# esp32_s20.net
KiCad netlist of a schematic drawn in EAGLE
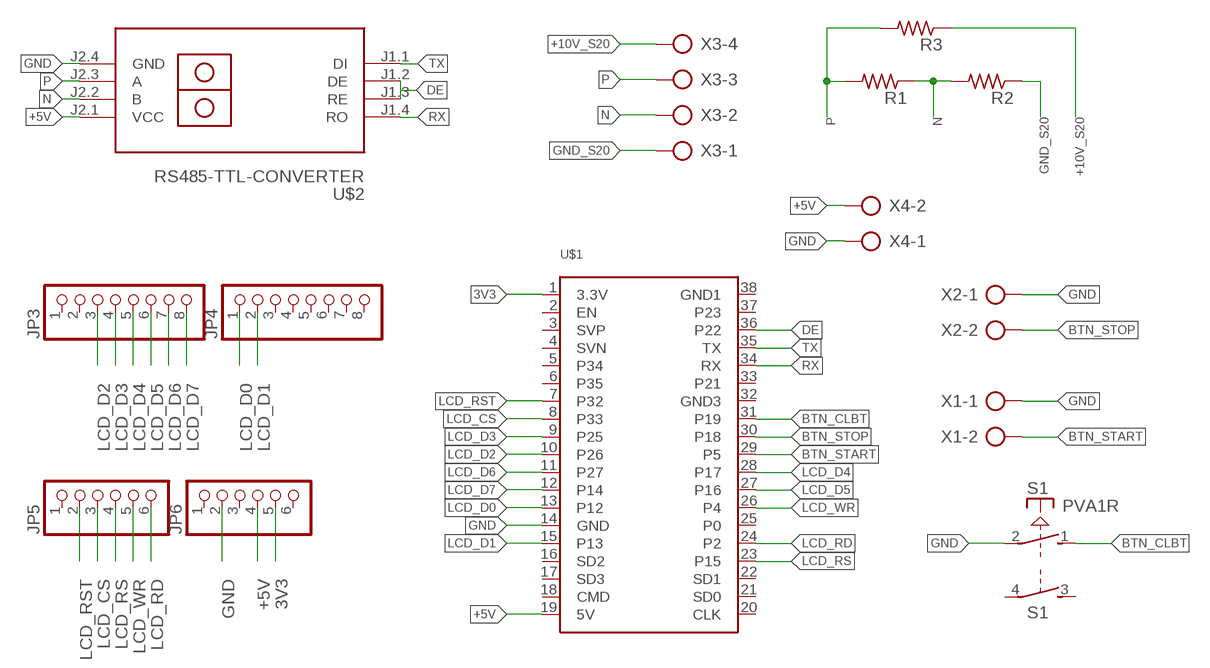
[diagram p0: schematic, sheet 1]

(export (version "E")
  (design (tool "Eeschema 10.0.6"))
  (components
    (comp (ref "JP3")
      (value "PINHD-1X8")
      (footprint "eagle-import:1X08")
      (libsource (lib "eagle-import") (part "PINHD-1X8"))
    )
    (comp (ref "JP4")
      (value "PINHD-1X8")
      (footprint "eagle-import:1X08")
      (libsource (lib "eagle-import") (part "PINHD-1X8"))
    )
    (comp (ref "JP5")
      (value "PINHD-1X6")
      (footprint "eagle-import:1X06")
      (libsource (lib "eagle-import") (part "PINHD-1X6"))
    )
    (comp (ref "JP6")
      (value "PINHD-1X6")
      (footprint "eagle-import:1X06")
      (libsource (lib "eagle-import") (part "PINHD-1X6"))
    )
    (comp (ref "R1")
      (value "R-US_0204/7")
      (footprint "eagle-import:0204_7")
      (libsource (lib "eagle-import") (part "R-US_0204/7"))
    )
    (comp (ref "R2")
      (value "R-US_0204/7")
      (footprint "eagle-import:0204_7")
      (libsource (lib "eagle-import") (part "R-US_0204/7"))
    )
    (comp (ref "R3")
      (value "R-US_0204/7")
      (footprint "eagle-import:0204_7")
      (libsource (lib "eagle-import") (part "R-US_0204/7"))
    )
    (comp (ref "S1")
      (value "PVA1R")
      (footprint "eagle-import:PVA1R")
      (libsource (lib "eagle-import") (part "PVA1R"))
    )
    (comp (ref "U$1")
      (value "ESP-32S")
      (footprint "eagle-import:BOARD")
      (libsource (lib "eagle-import") (part "ESP-32S"))
    )
    (comp (ref "U$2")
      (value "RS485-TTL-CONVERTER")
      (footprint "eagle-import:RS485-TTL-CONVERTER")
      (libsource (lib "eagle-import") (part "RS485-TTL-CONVERTER"))
    )
    (comp (ref "X1")
      (value "AK500/2-H")
      (footprint "eagle-import:AK500_2-H")
      (libsource (lib "eagle-import") (part "AK500/2-H"))
    )
    (comp (ref "X2")
      (value "AK500/2-H")
      (footprint "eagle-import:AK500_2-H")
      (libsource (lib "eagle-import") (part "AK500/2-H"))
    )
    (comp (ref "X3")
      (value "AK500/4-H")
      (footprint "eagle-import:AK500_4-H")
      (libsource (lib "eagle-import") (part "AK500/4-H"))
    )
    (comp (ref "X4")
      (value "AK500/2-H")
      (footprint "eagle-import:AK500_2-H")
      (libsource (lib "eagle-import") (part "AK500/2-H"))
    )
  )
  (nets
    (net (code "1") (name "+5V") (class "Default")
      (node (ref "JP6") (pin "4") (pinfunction "4_4") (pintype "passive"))
      (node (ref "U$1") (pin "19") (pinfunction "5V_19") (pintype "bidirectional"))
      (node (ref "U$2") (pin "J2.1") (pinfunction "VCC_J2.1") (pintype "power_in"))
      (node (ref "X4") (pin "2") (pinfunction "KL_2") (pintype "passive"))
    )
    (net (code "2") (name "+10V_S20") (class "Default")
      (node (ref "R3") (pin "1") (pinfunction "1_1") (pintype "passive"))
      (node (ref "X3") (pin "4") (pinfunction "KL_4") (pintype "passive"))
    )
    (net (code "3") (name "3V3") (class "Default")
      (node (ref "JP6") (pin "5") (pinfunction "5_5") (pintype "passive"))
      (node (ref "U$1") (pin "1") (pinfunction "3.3V_1") (pintype "bidirectional"))
    )
    (net (code "4") (name "BTN_CLBT") (class "Default")
      (node (ref "S1") (pin "1") (pinfunction "S_1") (pintype "passive"))
      (node (ref "U$1") (pin "31") (pinfunction "P19_31") (pintype "bidirectional"))
    )
    (net (code "5") (name "BTN_START") (class "Default")
      (node (ref "U$1") (pin "29") (pinfunction "P5_29") (pintype "bidirectional"))
      (node (ref "X1") (pin "2") (pinfunction "KL_2") (pintype "passive"))
    )
    (net (code "6") (name "BTN_STOP") (class "Default")
      (node (ref "U$1") (pin "30") (pinfunction "P18_30") (pintype "bidirectional"))
      (node (ref "X2") (pin "2") (pinfunction "KL_2") (pintype "passive"))
    )
    (net (code "7") (name "DE") (class "Default")
      (node (ref "U$1") (pin "36") (pinfunction "P22_36") (pintype "bidirectional"))
      (node (ref "U$2") (pin "J1.2") (pinfunction "DE_J1.2") (pintype "passive"))
      (node (ref "U$2") (pin "J1.3") (pinfunction "RE_J1.3") (pintype "passive"))
    )
    (net (code "8") (name "GND") (class "Default")
      (node (ref "JP6") (pin "2") (pinfunction "2_2") (pintype "passive"))
      (node (ref "S1") (pin "2") (pinfunction "P_2") (pintype "passive"))
      (node (ref "U$1") (pin "14") (pinfunction "GND_14") (pintype "bidirectional"))
      (node (ref "U$2") (pin "J2.4") (pinfunction "GND_J2.4") (pintype "power_in"))
      (node (ref "X1") (pin "1") (pinfunction "KL_1") (pintype "passive"))
      (node (ref "X2") (pin "1") (pinfunction "KL_1") (pintype "passive"))
      (node (ref "X4") (pin "1") (pinfunction "KL_1") (pintype "passive"))
    )
    (net (code "9") (name "GND_S20") (class "Default")
      (node (ref "R2") (pin "1") (pinfunction "1_1") (pintype "passive"))
      (node (ref "X3") (pin "1") (pinfunction "KL_1") (pintype "passive"))
    )
    (net (code "10") (name "LCD_CS") (class "Default")
      (node (ref "JP5") (pin "3") (pinfunction "3_3") (pintype "passive"))
      (node (ref "U$1") (pin "8") (pinfunction "P33_8") (pintype "bidirectional"))
    )
    (net (code "11") (name "LCD_D0") (class "Default")
      (node (ref "JP4") (pin "1") (pinfunction "1_1") (pintype "passive"))
      (node (ref "U$1") (pin "13") (pinfunction "P12_13") (pintype "bidirectional"))
    )
    (net (code "12") (name "LCD_D1") (class "Default")
      (node (ref "JP4") (pin "2") (pinfunction "2_2") (pintype "passive"))
      (node (ref "U$1") (pin "15") (pinfunction "P13_15") (pintype "bidirectional"))
    )
    (net (code "13") (name "LCD_D2") (class "Default")
      (node (ref "JP3") (pin "3") (pinfunction "3_3") (pintype "passive"))
      (node (ref "U$1") (pin "10") (pinfunction "P26_10") (pintype "bidirectional"))
    )
    (net (code "14") (name "LCD_D3") (class "Default")
      (node (ref "JP3") (pin "4") (pinfunction "4_4") (pintype "passive"))
      (node (ref "U$1") (pin "9") (pinfunction "P25_9") (pintype "bidirectional"))
    )
    (net (code "15") (name "LCD_D4") (class "Default")
      (node (ref "JP3") (pin "5") (pinfunction "5_5") (pintype "passive"))
      (node (ref "U$1") (pin "28") (pinfunction "P17_28") (pintype "bidirectional"))
    )
    (net (code "16") (name "LCD_D5") (class "Default")
      (node (ref "JP3") (pin "6") (pinfunction "6_6") (pintype "passive"))
      (node (ref "U$1") (pin "27") (pinfunction "P16_27") (pintype "bidirectional"))
    )
    (net (code "17") (name "LCD_D6") (class "Default")
      (node (ref "JP3") (pin "7") (pinfunction "7_7") (pintype "passive"))
      (node (ref "U$1") (pin "11") (pinfunction "P27_11") (pintype "bidirectional"))
    )
    (net (code "18") (name "LCD_D7") (class "Default")
      (node (ref "JP3") (pin "8") (pinfunction "8_8") (pintype "passive"))
      (node (ref "U$1") (pin "12") (pinfunction "P14_12") (pintype "bidirectional"))
    )
    (net (code "19") (name "LCD_RD") (class "Default")
      (node (ref "JP5") (pin "6") (pinfunction "6_6") (pintype "passive"))
      (node (ref "U$1") (pin "24") (pinfunction "P2_24") (pintype "bidirectional"))
    )
    (net (code "20") (name "LCD_RS") (class "Default")
      (node (ref "JP5") (pin "4") (pinfunction "4_4") (pintype "passive"))
      (node (ref "U$1") (pin "23") (pinfunction "P15_23") (pintype "bidirectional"))
    )
    (net (code "21") (name "LCD_RST") (class "Default")
      (node (ref "JP5") (pin "2") (pinfunction "2_2") (pintype "passive"))
      (node (ref "U$1") (pin "7") (pinfunction "P32_7") (pintype "bidirectional"))
    )
    (net (code "22") (name "LCD_WR") (class "Default")
      (node (ref "JP5") (pin "5") (pinfunction "5_5") (pintype "passive"))
      (node (ref "U$1") (pin "26") (pinfunction "P4_26") (pintype "bidirectional"))
    )
    (net (code "23") (name "N") (class "Default")
      (node (ref "R1") (pin "1") (pinfunction "1_1") (pintype "passive"))
      (node (ref "R2") (pin "2") (pinfunction "2_2") (pintype "passive"))
      (node (ref "U$2") (pin "J2.2") (pinfunction "B_J2.2") (pintype "passive"))
      (node (ref "X3") (pin "2") (pinfunction "KL_2") (pintype "passive"))
    )
    (net (code "24") (name "P") (class "Default")
      (node (ref "R1") (pin "2") (pinfunction "2_2") (pintype "passive"))
      (node (ref "R3") (pin "2") (pinfunction "2_2") (pintype "passive"))
      (node (ref "U$2") (pin "J2.3") (pinfunction "A_J2.3") (pintype "passive"))
      (node (ref "X3") (pin "3") (pinfunction "KL_3") (pintype "passive"))
    )
    (net (code "25") (name "RX") (class "Default")
      (node (ref "U$1") (pin "34") (pinfunction "RX_34") (pintype "bidirectional"))
      (node (ref "U$2") (pin "J1.4") (pinfunction "RO_J1.4") (pintype "passive"))
    )
    (net (code "26") (name "TX") (class "Default")
      (node (ref "U$1") (pin "35") (pinfunction "TX_35") (pintype "bidirectional"))
      (node (ref "U$2") (pin "J1.1") (pinfunction "DI_J1.1") (pintype "passive"))
    )
    (net (code "27") (name "unconnected-(JP3-Pad1)") (class "Default")
      (node (ref "JP3") (pin "1") (pinfunction "1_1") (pintype "passive"))
    )
    (net (code "28") (name "unconnected-(JP3-Pad2)") (class "Default")
      (node (ref "JP3") (pin "2") (pinfunction "2_2") (pintype "passive"))
    )
    (net (code "29") (name "unconnected-(JP4-Pad3)") (class "Default")
      (node (ref "JP4") (pin "3") (pinfunction "3_3") (pintype "passive"))
    )
    (net (code "30") (name "unconnected-(JP4-Pad4)") (class "Default")
      (node (ref "JP4") (pin "4") (pinfunction "4_4") (pintype "passive"))
    )
    (net (code "31") (name "unconnected-(JP4-Pad5)") (class "Default")
      (node (ref "JP4") (pin "5") (pinfunction "5_5") (pintype "passive"))
    )
    (net (code "32") (name "unconnected-(JP4-Pad6)") (class "Default")
      (node (ref "JP4") (pin "6") (pinfunction "6_6") (pintype "passive"))
    )
    (net (code "33") (name "unconnected-(JP4-Pad7)") (class "Default")
      (node (ref "JP4") (pin "7") (pinfunction "7_7") (pintype "passive"))
    )
    (net (code "34") (name "unconnected-(JP4-Pad8)") (class "Default")
      (node (ref "JP4") (pin "8") (pinfunction "8_8") (pintype "passive"))
    )
    (net (code "35") (name "unconnected-(JP5-Pad1)") (class "Default")
      (node (ref "JP5") (pin "1") (pinfunction "1_1") (pintype "passive"))
    )
    (net (code "36") (name "unconnected-(JP6-Pad1)") (class "Default")
      (node (ref "JP6") (pin "1") (pinfunction "1_1") (pintype "passive"))
    )
    (net (code "37") (name "unconnected-(JP6-Pad3)") (class "Default")
      (node (ref "JP6") (pin "3") (pinfunction "3_3") (pintype "passive"))
    )
    (net (code "38") (name "unconnected-(JP6-Pad6)") (class "Default")
      (node (ref "JP6") (pin "6") (pinfunction "6_6") (pintype "passive"))
    )
    (net (code "39") (name "unconnected-(S1B-P-Pad4)") (class "Default")
      (node (ref "S1") (pin "4") (pinfunction "P_4") (pintype "passive"))
    )
    (net (code "40") (name "unconnected-(S1B-S-Pad3)") (class "Default")
      (node (ref "S1") (pin "3") (pinfunction "S_3") (pintype "passive"))
    )
    (net (code "41") (name "unconnected-(U$1-CLK-Pad20)") (class "Default")
      (node (ref "U$1") (pin "20") (pinfunction "CLK_20") (pintype "bidirectional"))
    )
    (net (code "42") (name "unconnected-(U$1-CMD-Pad18)") (class "Default")
      (node (ref "U$1") (pin "18") (pinfunction "CMD_18") (pintype "bidirectional"))
    )
    (net (code "43") (name "unconnected-(U$1-EN-Pad2)") (class "Default")
      (node (ref "U$1") (pin "2") (pinfunction "EN_2") (pintype "bidirectional"))
    )
    (net (code "44") (name "unconnected-(U$1-GND1-Pad38)") (class "Default")
      (node (ref "U$1") (pin "38") (pinfunction "GND1_38") (pintype "bidirectional"))
    )
    (net (code "45") (name "unconnected-(U$1-GND3-Pad32)") (class "Default")
      (node (ref "U$1") (pin "32") (pinfunction "GND3_32") (pintype "bidirectional"))
    )
    (net (code "46") (name "unconnected-(U$1-P0-Pad25)") (class "Default")
      (node (ref "U$1") (pin "25") (pinfunction "P0_25") (pintype "bidirectional"))
    )
    (net (code "47") (name "unconnected-(U$1-P21-Pad33)") (class "Default")
      (node (ref "U$1") (pin "33") (pinfunction "P21_33") (pintype "bidirectional"))
    )
    (net (code "48") (name "unconnected-(U$1-P23-Pad37)") (class "Default")
      (node (ref "U$1") (pin "37") (pinfunction "P23_37") (pintype "bidirectional"))
    )
    (net (code "49") (name "unconnected-(U$1-P34-Pad5)") (class "Default")
      (node (ref "U$1") (pin "5") (pinfunction "P34_5") (pintype "bidirectional"))
    )
    (net (code "50") (name "unconnected-(U$1-P35-Pad6)") (class "Default")
      (node (ref "U$1") (pin "6") (pinfunction "P35_6") (pintype "bidirectional"))
    )
    (net (code "51") (name "unconnected-(U$1-SD0-Pad21)") (class "Default")
      (node (ref "U$1") (pin "21") (pinfunction "SD0_21") (pintype "bidirectional"))
    )
    (net (code "52") (name "unconnected-(U$1-SD1-Pad22)") (class "Default")
      (node (ref "U$1") (pin "22") (pinfunction "SD1_22") (pintype "bidirectional"))
    )
    (net (code "53") (name "unconnected-(U$1-SD2-Pad16)") (class "Default")
      (node (ref "U$1") (pin "16") (pinfunction "SD2_16") (pintype "bidirectional"))
    )
    (net (code "54") (name "unconnected-(U$1-SD3-Pad17)") (class "Default")
      (node (ref "U$1") (pin "17") (pinfunction "SD3_17") (pintype "bidirectional"))
    )
    (net (code "55") (name "unconnected-(U$1-SVN-Pad4)") (class "Default")
      (node (ref "U$1") (pin "4") (pinfunction "SVN_4") (pintype "bidirectional"))
    )
    (net (code "56") (name "unconnected-(U$1-SVP-Pad3)") (class "Default")
      (node (ref "U$1") (pin "3") (pinfunction "SVP_3") (pintype "bidirectional"))
    )
  )
)
